# Sheet3.net
KiCad netlist of a schematic drawn in Altium Designer
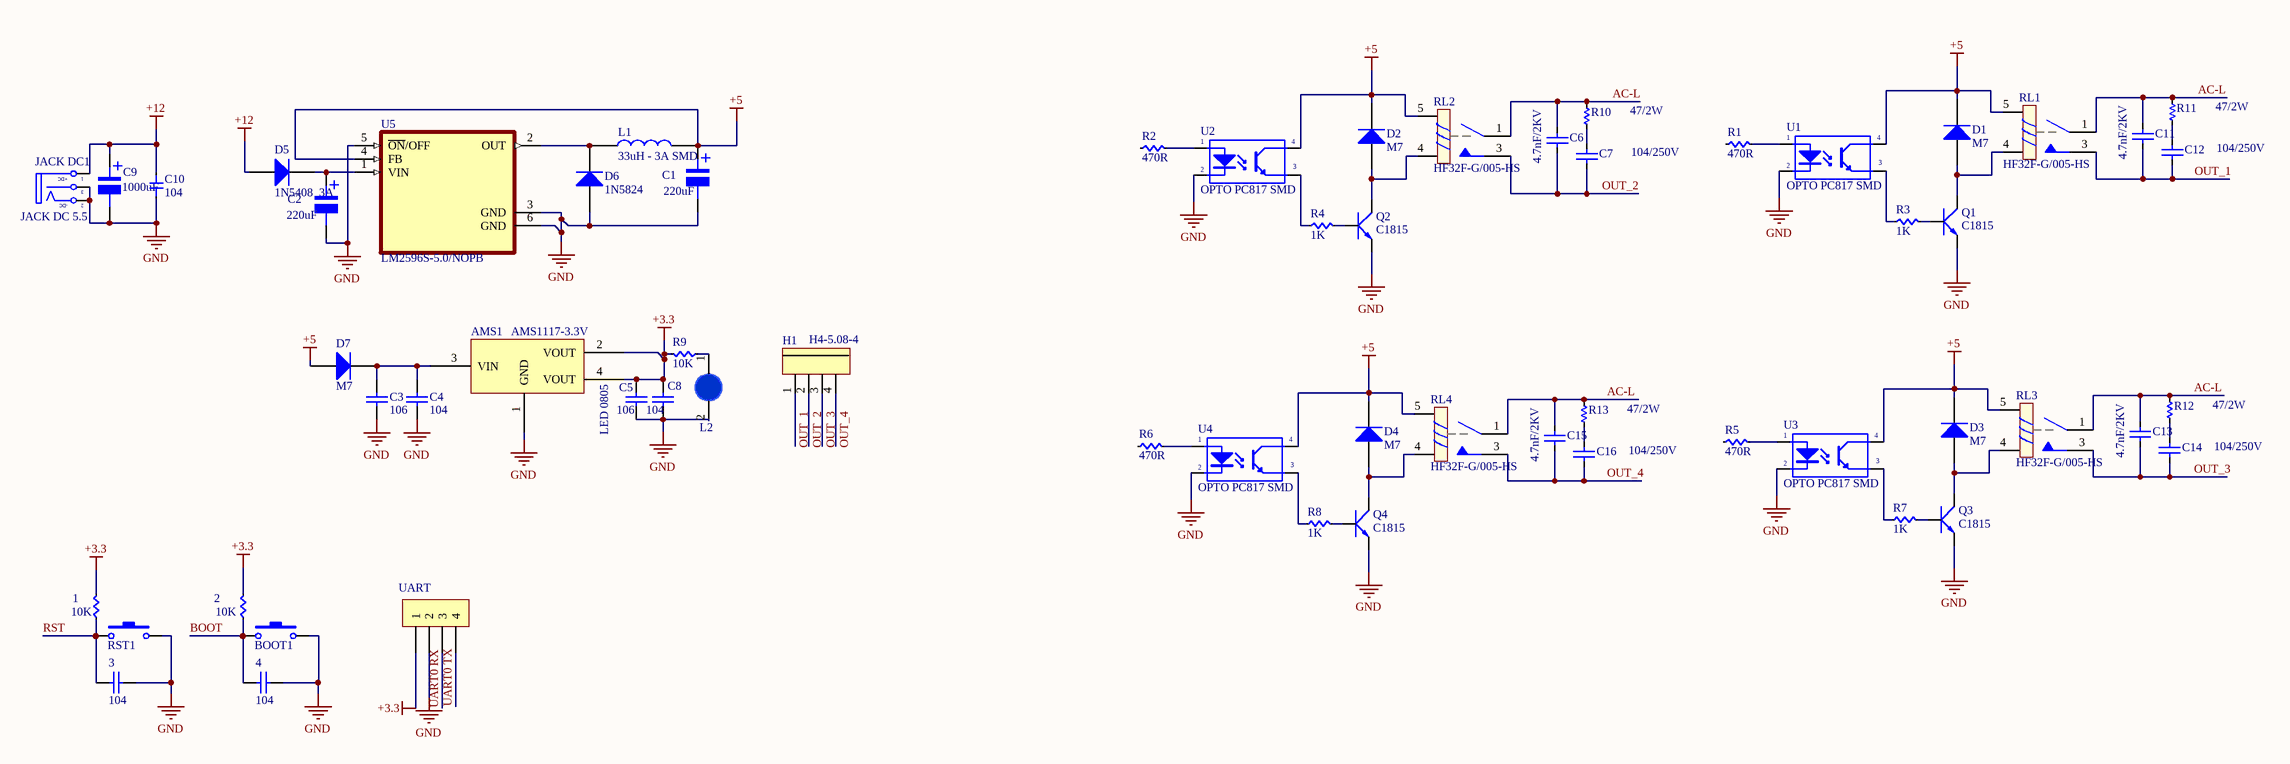
[diagram p0: Sheet3.SchDoc]

(export (version "E")
  (design (tool "Eeschema 10.0.6"))
  (components
    (comp (ref "1")
      (value "10K")
      (footprint "RES 0805")
      (description "RES SMD 0805")
      (fields
        (field (name "MANUFACTURER") "Vishay Dale")
        (field (name "MANUFACTURER PART NUMBER") "CRCW040210K0FKED")
      )
      (libsource (lib "Altium_Lib_by_KhueNguyenCreator") (part "RES 0805"))
    )
    (comp (ref "2")
      (value "10K")
      (footprint "RES 0805")
      (description "RES SMD 0805")
      (fields
        (field (name "MANUFACTURER") "Vishay Dale")
        (field (name "MANUFACTURER PART NUMBER") "CRCW040210K0FKED")
      )
      (libsource (lib "Altium_Lib_by_KhueNguyenCreator") (part "RES 0805"))
    )
    (comp (ref "3")
      (value "104")
      (footprint "tu 0805")
      (description "Dán")
      (libsource (lib "Altium_Lib_by_KhueNguyenCreator") (part "Tu 0805 104 50V 10%"))
    )
    (comp (ref "4")
      (value "104")
      (footprint "tu 0805")
      (description "Dán")
      (libsource (lib "Altium_Lib_by_KhueNguyenCreator") (part "Tu 0805 104 50V 10%"))
    )
    (comp (ref "AMS1")
      (value "AMS1117-3.3V")
      (footprint "SOT223")
      (description "Dán")
      (libsource (lib "Altium_Lib_by_KhueNguyenCreator") (part "AMS1117 SMD"))
    )
    (comp (ref "BOOT1")
      (value "Nut Nhan 2 Chan SMD 3x6x2.5")
      (footprint "Nut Nhan 2 Chan SMD 3x6x2.5")
      (libsource (lib "Altium_Lib_by_KhueNguyenCreator") (part "Nut Nhan 2 Chan SMD 3x6x2.5"))
    )
    (comp (ref "C1")
      (value "220uF")
      (footprint "tu nhom 10 (G)")
      (description "Dán")
      (libsource (lib "Altium_Lib_by_KhueNguyenCreator") (part "Tu Nhom 470uF 35V"))
    )
    (comp (ref "C2")
      (value "220uF")
      (footprint "tu nhom 10 (G)")
      (description "Dán")
      (libsource (lib "Altium_Lib_by_KhueNguyenCreator") (part "Tu Nhom 470uF 35V"))
    )
    (comp (ref "C3")
      (value "106")
      (footprint "tu 0805")
      (description "Dán")
      (libsource (lib "Altium_Lib_by_KhueNguyenCreator") (part "Tu 0805 106 16V 10%"))
    )
    (comp (ref "C4")
      (value "104")
      (footprint "tu 0805")
      (description "Dán")
      (libsource (lib "Altium_Lib_by_KhueNguyenCreator") (part "Tu 0805 104 50V 10%"))
    )
    (comp (ref "C5")
      (value "106")
      (footprint "tu 0805")
      (description "Dán")
      (libsource (lib "Altium_Lib_by_KhueNguyenCreator") (part "Tu 0805 106 16V 10%"))
    )
    (comp (ref "C6")
      (value "4.7nF/2KV")
      (footprint "Cap 6.35mm")
      (description "Capacitor")
      (libsource (lib "iuh-thuc-hanh") (part "CN"))
    )
    (comp (ref "C7")
      (value "104/250V")
      (footprint "Cap 10mm")
      (description "Capacitor")
      (libsource (lib "iuh-thuc-hanh") (part "CN"))
    )
    (comp (ref "C8")
      (value "104")
      (footprint "tu 0805")
      (description "Dán")
      (libsource (lib "Altium_Lib_by_KhueNguyenCreator") (part "Tu 0805 106 16V 10%"))
    )
    (comp (ref "C9")
      (value "1000uF")
      (footprint "tu nhom 10 (G)")
      (description "Dán")
      (libsource (lib "Altium_Lib_by_KhueNguyenCreator") (part "Tu Nhom 1000uF 10V"))
    )
    (comp (ref "C10")
      (value "104")
      (footprint "Cap 0603")
      (description "Capacitor SMD 0603")
      (libsource (lib "Altium_Lib_by_KhueNguyenCreator") (part "Cap 0603"))
    )
    (comp (ref "C11")
      (value "4.7nF/2KV")
      (footprint "Cap 6.35mm")
      (description "Capacitor")
      (libsource (lib "iuh-thuc-hanh") (part "CN"))
    )
    (comp (ref "C12")
      (value "104/250V")
      (footprint "Cap 10mm")
      (description "Capacitor")
      (libsource (lib "iuh-thuc-hanh") (part "CN"))
    )
    (comp (ref "C13")
      (value "4.7nF/2KV")
      (footprint "Cap 6.35mm")
      (description "Capacitor")
      (libsource (lib "iuh-thuc-hanh") (part "CN"))
    )
    (comp (ref "C14")
      (value "104/250V")
      (footprint "Cap 10mm")
      (description "Capacitor")
      (libsource (lib "iuh-thuc-hanh") (part "CN"))
    )
    (comp (ref "C15")
      (value "4.7nF/2KV")
      (footprint "Cap 6.35mm")
      (description "Capacitor")
      (libsource (lib "iuh-thuc-hanh") (part "CN"))
    )
    (comp (ref "C16")
      (value "104/250V")
      (footprint "Cap 10mm")
      (description "Capacitor")
      (libsource (lib "iuh-thuc-hanh") (part "CN"))
    )
    (comp (ref "D1")
      (value "M7")
      (footprint "DIODE SMA")
      (description "Dán")
      (libsource (lib "Altium_Lib_by_KhueNguyenCreator") (part "Diode M7 ( 4007 )"))
    )
    (comp (ref "D2")
      (value "M7")
      (footprint "DIODE SMA")
      (description "Dán")
      (libsource (lib "Altium_Lib_by_KhueNguyenCreator") (part "Diode M7 ( 4007 )"))
    )
    (comp (ref "D3")
      (value "M7")
      (footprint "DIODE SMA")
      (description "Dán")
      (libsource (lib "Altium_Lib_by_KhueNguyenCreator") (part "Diode M7 ( 4007 )"))
    )
    (comp (ref "D4")
      (value "M7")
      (footprint "DIODE SMA")
      (description "Dán")
      (libsource (lib "Altium_Lib_by_KhueNguyenCreator") (part "Diode M7 ( 4007 )"))
    )
    (comp (ref "D5")
      (value "1N5408  3A")
      (footprint "DIODE SMA")
      (description "Dán")
      (libsource (lib "Altium_Lib_by_KhueNguyenCreator") (part "Diode M7 ( 4007 )"))
    )
    (comp (ref "D6")
      (value "1N5824")
      (footprint "DIODE SMA")
      (description "Dán")
      (libsource (lib "Altium_Lib_by_KhueNguyenCreator") (part "Diode SS34 ( 1N5822 )"))
    )
    (comp (ref "D7")
      (value "M7")
      (footprint "DIODE SMA")
      (description "Dán")
      (libsource (lib "Altium_Lib_by_KhueNguyenCreator") (part "Diode M7 ( 4007 )"))
    )
    (comp (ref "H1")
      (value "H4-5.08-4")
      (footprint "KF-5.08-4")
      (libsource (lib "iuh-thuc-hanh") (part "KF-5.08-4-R Cong"))
    )
    (comp (ref "H2")
      (value "UART")
      (footprint "XH2.54M-4")
      (description "Cắm")
      (libsource (lib "Altium_Lib_by_KhueNguyenCreator") (part "Header 4P 2.54 Duc Thang"))
    )
    (comp (ref "JACK DC1")
      (value "JACK DC 5.5")
      (footprint "JACK DC 5.5")
      (libsource (lib "Altium_Lib_by_KhueNguyenCreator") (part "JACK DC 5.5"))
    )
    (comp (ref "L1")
      (value "33uH - 3A SMD")
      (footprint "Cuon Cam 12x12x10")
      (description "Dán")
      (libsource (lib "Altium_Lib_by_KhueNguyenCreator") (part "CUON CAM 100uH SMD"))
    )
    (comp (ref "L2")
      (value "LED 0805")
      (footprint "LED-0805-Blue")
      (description "Dán")
      (libsource (lib "Altium_Lib_by_KhueNguyenCreator") (part "LED 0805 Xanh Duong"))
    )
    (comp (ref "Q1")
      (value "C1815")
      (footprint "QTO-92")
      (description "NPN 600mW, ECB")
      (libsource (lib "syhaunguyen") (part "C1815"))
    )
    (comp (ref "Q2")
      (value "C1815")
      (footprint "QTO-92")
      (description "NPN 600mW, ECB")
      (libsource (lib "syhaunguyen") (part "C1815"))
    )
    (comp (ref "Q3")
      (value "C1815")
      (footprint "QTO-92")
      (description "NPN 600mW, ECB")
      (libsource (lib "syhaunguyen") (part "C1815"))
    )
    (comp (ref "Q4")
      (value "C1815")
      (footprint "QTO-92")
      (description "NPN 600mW, ECB")
      (libsource (lib "syhaunguyen") (part "C1815"))
    )
    (comp (ref "R1")
      (value "470R")
      (footprint "RES 0805")
      (description "RES SMD 0805")
      (fields
        (field (name "MANUFACTURER") "Vishay Dale")
        (field (name "MANUFACTURER PART NUMBER") "CRCW040210K0FKED")
      )
      (libsource (lib "Altium_Lib_by_KhueNguyenCreator") (part "RES 0805"))
    )
    (comp (ref "R2")
      (value "470R")
      (footprint "RES 0805")
      (description "RES SMD 0805")
      (fields
        (field (name "MANUFACTURER") "Vishay Dale")
        (field (name "MANUFACTURER PART NUMBER") "CRCW040210K0FKED")
      )
      (libsource (lib "Altium_Lib_by_KhueNguyenCreator") (part "RES 0805"))
    )
    (comp (ref "R3")
      (value "1K")
      (footprint "RES 0805")
      (description "RES SMD 0805")
      (fields
        (field (name "MANUFACTURER") "Vishay Dale")
        (field (name "MANUFACTURER PART NUMBER") "CRCW040210K0FKED")
      )
      (libsource (lib "Altium_Lib_by_KhueNguyenCreator") (part "RES 0805"))
    )
    (comp (ref "R4")
      (value "1K")
      (footprint "RES 0805")
      (description "RES SMD 0805")
      (fields
        (field (name "MANUFACTURER") "Vishay Dale")
        (field (name "MANUFACTURER PART NUMBER") "CRCW040210K0FKED")
      )
      (libsource (lib "Altium_Lib_by_KhueNguyenCreator") (part "RES 0805"))
    )
    (comp (ref "R5")
      (value "470R")
      (footprint "RES 0805")
      (description "RES SMD 0805")
      (fields
        (field (name "MANUFACTURER") "Vishay Dale")
        (field (name "MANUFACTURER PART NUMBER") "CRCW040210K0FKED")
      )
      (libsource (lib "Altium_Lib_by_KhueNguyenCreator") (part "RES 0805"))
    )
    (comp (ref "R6")
      (value "470R")
      (footprint "RES 0805")
      (description "RES SMD 0805")
      (fields
        (field (name "MANUFACTURER") "Vishay Dale")
        (field (name "MANUFACTURER PART NUMBER") "CRCW040210K0FKED")
      )
      (libsource (lib "Altium_Lib_by_KhueNguyenCreator") (part "RES 0805"))
    )
    (comp (ref "R7")
      (value "1K")
      (footprint "RES 0805")
      (description "RES SMD 0805")
      (fields
        (field (name "MANUFACTURER") "Vishay Dale")
        (field (name "MANUFACTURER PART NUMBER") "CRCW040210K0FKED")
      )
      (libsource (lib "Altium_Lib_by_KhueNguyenCreator") (part "RES 0805"))
    )
    (comp (ref "R8")
      (value "1K")
      (footprint "RES 0805")
      (description "RES SMD 0805")
      (fields
        (field (name "MANUFACTURER") "Vishay Dale")
        (field (name "MANUFACTURER PART NUMBER") "CRCW040210K0FKED")
      )
      (libsource (lib "Altium_Lib_by_KhueNguyenCreator") (part "RES 0805"))
    )
    (comp (ref "R9")
      (value "10K")
      (footprint "RES 0805")
      (description "RES SMD 0805")
      (fields
        (field (name "MANUFACTURER") "Vishay Dale")
        (field (name "MANUFACTURER PART NUMBER") "CRCW040210K0FKED")
      )
      (libsource (lib "Altium_Lib_by_KhueNguyenCreator") (part "RES 0805"))
    )
    (comp (ref "R10") (value "47/2W") (footprint "RES-1W") (libsource (lib "iuh-thuc-hanh") (part "Res")))
    (comp (ref "R11") (value "47/2W") (footprint "RES-1W") (libsource (lib "iuh-thuc-hanh") (part "Res")))
    (comp (ref "R12") (value "47/2W") (footprint "RES-1W") (libsource (lib "iuh-thuc-hanh") (part "Res")))
    (comp (ref "R13") (value "47/2W") (footprint "RES-1W") (libsource (lib "iuh-thuc-hanh") (part "Res")))
    (comp (ref "RL1")
      (value "HF32F-G/005-HS")
      (footprint "HF32F-G")
      (description "Relay hongfa 10A 4P HF32F-G/005-HS")
      (libsource (lib "iuh-thuc-hanh") (part "Relay HF 10A"))
    )
    (comp (ref "RL2")
      (value "HF32F-G/005-HS")
      (footprint "HF32F-G")
      (description "Relay hongfa 10A 4P HF32F-G/005-HS")
      (libsource (lib "iuh-thuc-hanh") (part "Relay HF 10A"))
    )
    (comp (ref "RL3")
      (value "HF32F-G/005-HS")
      (footprint "HF32F-G")
      (description "Relay hongfa 10A 4P HF32F-G/005-HS")
      (libsource (lib "iuh-thuc-hanh") (part "Relay HF 10A"))
    )
    (comp (ref "RL4")
      (value "HF32F-G/005-HS")
      (footprint "HF32F-G")
      (description "Relay hongfa 10A 4P HF32F-G/005-HS")
      (libsource (lib "iuh-thuc-hanh") (part "Relay HF 10A"))
    )
    (comp (ref "RST1")
      (value "Nut Nhan 2 Chan SMD 3x6x2.5")
      (footprint "Nut Nhan 2 Chan SMD 3x6x2.5")
      (libsource (lib "Altium_Lib_by_KhueNguyenCreator") (part "Nut Nhan 2 Chan SMD 3x6x2.5"))
    )
    (comp (ref "U1")
      (value "OPTO PC817 SMD")
      (footprint "SOP4")
      (description "Single Opto")
      (libsource (lib "Altium_Lib_by_KhueNguyenCreator") (part "OPTO PC817 SMD"))
    )
    (comp (ref "U2")
      (value "OPTO PC817 SMD")
      (footprint "SOP4")
      (description "Single Opto")
      (libsource (lib "Altium_Lib_by_KhueNguyenCreator") (part "OPTO PC817 SMD"))
    )
    (comp (ref "U3")
      (value "OPTO PC817 SMD")
      (footprint "SOP4")
      (description "Single Opto")
      (libsource (lib "Altium_Lib_by_KhueNguyenCreator") (part "OPTO PC817 SMD"))
    )
    (comp (ref "U4")
      (value "OPTO PC817 SMD")
      (footprint "SOP4")
      (description "Single Opto")
      (libsource (lib "Altium_Lib_by_KhueNguyenCreator") (part "OPTO PC817 SMD"))
    )
    (comp (ref "U5")
      (value "LM2596S-5.0/NOPB")
      (footprint "VREG_LM2596S-12/NOPB")
      (description "SIMPLE SWITCHERÂ® 4.5V to 40V, 3A Low Component Count Step-Down Regulator")
      (fields (field (name "MF") "Texas Instruments") (field (name "MP") "LM2596S-12/NOPB"))
      (libsource (lib "TuHap") (part "LM2596S-12/NOPB"))
    )
  )
  (nets
    (net (code "1") (name "+3.3") (class "Default")
      (node (ref "1") (pin "2") (pinfunction "2_2") (pintype "passive"))
      (node (ref "2") (pin "2") (pinfunction "2_2") (pintype "passive"))
      (node (ref "AMS1") (pin "2") (pinfunction "VOUT_2") (pintype "passive"))
      (node (ref "AMS1") (pin "4") (pinfunction "VOUT_4") (pintype "passive"))
      (node (ref "C5") (pin "1") (pinfunction "1_1") (pintype "passive"))
      (node (ref "C8") (pin "1") (pinfunction "1_1") (pintype "passive"))
      (node (ref "H2") (pin "1") (pinfunction "1_1") (pintype "passive"))
      (node (ref "R9") (pin "2") (pinfunction "2_2") (pintype "passive"))
    )
    (net (code "2") (name "+5") (class "Default")
      (node (ref "C1") (pin "1") (pinfunction "1_1") (pintype "passive"))
      (node (ref "D1") (pin "2") (pinfunction "K_2") (pintype "passive"))
      (node (ref "D2") (pin "2") (pinfunction "K_2") (pintype "passive"))
      (node (ref "D3") (pin "2") (pinfunction "K_2") (pintype "passive"))
      (node (ref "D4") (pin "2") (pinfunction "K_2") (pintype "passive"))
      (node (ref "D7") (pin "1") (pinfunction "A_1") (pintype "passive"))
      (node (ref "L1") (pin "2") (pinfunction "2_2") (pintype "passive"))
      (node (ref "RL1") (pin "5") (pinfunction "5_5") (pintype "passive"))
      (node (ref "RL2") (pin "5") (pinfunction "5_5") (pintype "passive"))
      (node (ref "RL3") (pin "5") (pinfunction "5_5") (pintype "passive"))
      (node (ref "RL4") (pin "5") (pinfunction "5_5") (pintype "passive"))
      (node (ref "U1") (pin "4") (pinfunction "C_4") (pintype "passive"))
      (node (ref "U2") (pin "4") (pinfunction "C_4") (pintype "passive"))
      (node (ref "U3") (pin "4") (pinfunction "C_4") (pintype "passive"))
      (node (ref "U4") (pin "4") (pinfunction "C_4") (pintype "passive"))
      (node (ref "U5") (pin "4") (pinfunction "FB_4") (pintype "input"))
    )
    (net (code "3") (name "+12") (class "Default")
      (node (ref "C10") (pin "1") (pinfunction "1_1") (pintype "passive"))
      (node (ref "C9") (pin "1") (pinfunction "1_1") (pintype "passive"))
      (node (ref "D5") (pin "1") (pinfunction "A_1") (pintype "passive"))
      (node (ref "JACK DC1") (pin "1") (pinfunction "T_1") (pintype "passive"))
    )
    (net (code "4") (name "/AC-L") (class "Default")
      (node (ref "C11") (pin "1") (pinfunction "1_1") (pintype "passive"))
      (node (ref "C13") (pin "1") (pinfunction "1_1") (pintype "passive"))
      (node (ref "C15") (pin "1") (pinfunction "1_1") (pintype "passive"))
      (node (ref "C6") (pin "1") (pinfunction "1_1") (pintype "passive"))
      (node (ref "R10") (pin "1") (pinfunction "1_1") (pintype "passive"))
      (node (ref "R11") (pin "1") (pinfunction "1_1") (pintype "passive"))
      (node (ref "R12") (pin "1") (pinfunction "1_1") (pintype "passive"))
      (node (ref "R13") (pin "1") (pinfunction "1_1") (pintype "passive"))
      (node (ref "RL1") (pin "1") (pinfunction "1_1") (pintype "passive"))
      (node (ref "RL2") (pin "1") (pinfunction "1_1") (pintype "passive"))
      (node (ref "RL3") (pin "1") (pinfunction "1_1") (pintype "passive"))
      (node (ref "RL4") (pin "1") (pinfunction "1_1") (pintype "passive"))
    )
    (net (code "5") (name "/BOOT") (class "Default")
      (node (ref "2") (pin "1") (pinfunction "1_1") (pintype "passive"))
      (node (ref "4") (pin "1") (pinfunction "1_1") (pintype "passive"))
      (node (ref "BOOT1") (pin "1") (pinfunction "1_1") (pintype "passive"))
    )
    (net (code "6") (name "/OUT_1") (class "Default")
      (node (ref "C11") (pin "2") (pinfunction "2_2") (pintype "passive"))
      (node (ref "C12") (pin "1") (pinfunction "1_1") (pintype "passive"))
      (node (ref "H1") (pin "1") (pinfunction "1_1") (pintype "passive"))
      (node (ref "RL1") (pin "3") (pinfunction "3_3") (pintype "passive"))
    )
    (net (code "7") (name "/OUT_2") (class "Default")
      (node (ref "C6") (pin "2") (pinfunction "2_2") (pintype "passive"))
      (node (ref "C7") (pin "1") (pinfunction "1_1") (pintype "passive"))
      (node (ref "H1") (pin "2") (pinfunction "2_2") (pintype "passive"))
      (node (ref "RL2") (pin "3") (pinfunction "3_3") (pintype "passive"))
    )
    (net (code "8") (name "/OUT_3") (class "Default")
      (node (ref "C13") (pin "2") (pinfunction "2_2") (pintype "passive"))
      (node (ref "C14") (pin "1") (pinfunction "1_1") (pintype "passive"))
      (node (ref "H1") (pin "3") (pinfunction "3_3") (pintype "passive"))
      (node (ref "RL3") (pin "3") (pinfunction "3_3") (pintype "passive"))
    )
    (net (code "9") (name "/OUT_4") (class "Default")
      (node (ref "C15") (pin "2") (pinfunction "2_2") (pintype "passive"))
      (node (ref "C16") (pin "1") (pinfunction "1_1") (pintype "passive"))
      (node (ref "H1") (pin "4") (pinfunction "4_4") (pintype "passive"))
      (node (ref "RL4") (pin "3") (pinfunction "3_3") (pintype "passive"))
    )
    (net (code "10") (name "/RST") (class "Default")
      (node (ref "1") (pin "1") (pinfunction "1_1") (pintype "passive"))
      (node (ref "3") (pin "1") (pinfunction "1_1") (pintype "passive"))
      (node (ref "RST1") (pin "1") (pinfunction "1_1") (pintype "passive"))
    )
    (net (code "11") (name "/UART0 RX") (class "Default")
      (node (ref "H2") (pin "3") (pinfunction "3_3") (pintype "passive"))
    )
    (net (code "12") (name "/UART0 TX") (class "Default")
      (node (ref "H2") (pin "4") (pinfunction "4_4") (pintype "passive"))
    )
    (net (code "13") (name "GND") (class "Default")
      (node (ref "3") (pin "2") (pinfunction "2_2") (pintype "passive"))
      (node (ref "4") (pin "2") (pinfunction "2_2") (pintype "passive"))
      (node (ref "AMS1") (pin "1") (pinfunction "GND_1") (pintype "passive"))
      (node (ref "BOOT1") (pin "2") (pinfunction "2_2") (pintype "passive"))
      (node (ref "C1") (pin "2") (pinfunction "2_2") (pintype "passive"))
      (node (ref "C10") (pin "2") (pinfunction "2_2") (pintype "passive"))
      (node (ref "C2") (pin "2") (pinfunction "2_2") (pintype "passive"))
      (node (ref "C3") (pin "2") (pinfunction "2_2") (pintype "passive"))
      (node (ref "C4") (pin "2") (pinfunction "2_2") (pintype "passive"))
      (node (ref "C5") (pin "2") (pinfunction "2_2") (pintype "passive"))
      (node (ref "C8") (pin "2") (pinfunction "2_2") (pintype "passive"))
      (node (ref "C9") (pin "2") (pinfunction "2_2") (pintype "passive"))
      (node (ref "D6") (pin "1") (pinfunction "A_1") (pintype "passive"))
      (node (ref "H2") (pin "2") (pinfunction "2_2") (pintype "passive"))
      (node (ref "JACK DC1") (pin "2") (pinfunction "TN_2") (pintype "passive"))
      (node (ref "JACK DC1") (pin "3") (pinfunction "S_3") (pintype "power_in"))
      (node (ref "L2") (pin "2") (pinfunction "K_2") (pintype "passive"))
      (node (ref "Q1") (pin "1") (pinfunction "E_1") (pintype "passive"))
      (node (ref "Q2") (pin "1") (pinfunction "E_1") (pintype "passive"))
      (node (ref "Q3") (pin "1") (pinfunction "E_1") (pintype "passive"))
      (node (ref "Q4") (pin "1") (pinfunction "E_1") (pintype "passive"))
      (node (ref "RST1") (pin "2") (pinfunction "2_2") (pintype "passive"))
      (node (ref "U1") (pin "2") (pinfunction "K_2") (pintype "passive"))
      (node (ref "U2") (pin "2") (pinfunction "K_2") (pintype "passive"))
      (node (ref "U3") (pin "2") (pinfunction "K_2") (pintype "passive"))
      (node (ref "U4") (pin "2") (pinfunction "K_2") (pintype "passive"))
      (node (ref "U5") (pin "3") (pinfunction "GND_3") (pintype "power_in"))
      (node (ref "U5") (pin "5") (pinfunction "~{ON}/OFF_5") (pintype "input"))
      (node (ref "U5") (pin "6") (pinfunction "GND_6") (pintype "power_in"))
    )
    (net (code "14") (name "Net-(AMS1-VIN)") (class "Default")
      (node (ref "AMS1") (pin "3") (pinfunction "VIN_3") (pintype "passive"))
      (node (ref "C3") (pin "1") (pinfunction "1_1") (pintype "passive"))
      (node (ref "C4") (pin "1") (pinfunction "1_1") (pintype "passive"))
      (node (ref "D7") (pin "2") (pinfunction "K_2") (pintype "passive"))
    )
    (net (code "15") (name "Net-(C7-Pad2)") (class "Default")
      (node (ref "C7") (pin "2") (pinfunction "2_2") (pintype "passive"))
      (node (ref "R10") (pin "2") (pinfunction "2_2") (pintype "passive"))
    )
    (net (code "16") (name "Net-(C12-Pad2)") (class "Default")
      (node (ref "C12") (pin "2") (pinfunction "2_2") (pintype "passive"))
      (node (ref "R11") (pin "2") (pinfunction "2_2") (pintype "passive"))
    )
    (net (code "17") (name "Net-(C14-Pad2)") (class "Default")
      (node (ref "C14") (pin "2") (pinfunction "2_2") (pintype "passive"))
      (node (ref "R12") (pin "2") (pinfunction "2_2") (pintype "passive"))
    )
    (net (code "18") (name "Net-(C16-Pad2)") (class "Default")
      (node (ref "C16") (pin "2") (pinfunction "2_2") (pintype "passive"))
      (node (ref "R13") (pin "2") (pinfunction "2_2") (pintype "passive"))
    )
    (net (code "19") (name "Net-(D1-A)") (class "Default")
      (node (ref "D1") (pin "1") (pinfunction "A_1") (pintype "passive"))
      (node (ref "Q1") (pin "2") (pinfunction "C_2") (pintype "passive"))
      (node (ref "RL1") (pin "4") (pinfunction "4_4") (pintype "passive"))
    )
    (net (code "20") (name "Net-(D2-A)") (class "Default")
      (node (ref "D2") (pin "1") (pinfunction "A_1") (pintype "passive"))
      (node (ref "Q2") (pin "2") (pinfunction "C_2") (pintype "passive"))
      (node (ref "RL2") (pin "4") (pinfunction "4_4") (pintype "passive"))
    )
    (net (code "21") (name "Net-(D3-A)") (class "Default")
      (node (ref "D3") (pin "1") (pinfunction "A_1") (pintype "passive"))
      (node (ref "Q3") (pin "2") (pinfunction "C_2") (pintype "passive"))
      (node (ref "RL3") (pin "4") (pinfunction "4_4") (pintype "passive"))
    )
    (net (code "22") (name "Net-(D4-A)") (class "Default")
      (node (ref "D4") (pin "1") (pinfunction "A_1") (pintype "passive"))
      (node (ref "Q4") (pin "2") (pinfunction "C_2") (pintype "passive"))
      (node (ref "RL4") (pin "4") (pinfunction "4_4") (pintype "passive"))
    )
    (net (code "23") (name "Net-(D5-K)") (class "Default")
      (node (ref "C2") (pin "1") (pinfunction "1_1") (pintype "passive"))
      (node (ref "D5") (pin "2") (pinfunction "K_2") (pintype "passive"))
      (node (ref "U5") (pin "1") (pinfunction "VIN_1") (pintype "input"))
    )
    (net (code "24") (name "Net-(D6-K)") (class "Default")
      (node (ref "D6") (pin "2") (pinfunction "K_2") (pintype "passive"))
      (node (ref "L1") (pin "1") (pinfunction "1_1") (pintype "passive"))
      (node (ref "U5") (pin "2") (pinfunction "OUT_2") (pintype "output"))
    )
    (net (code "25") (name "Net-(L2-A)") (class "Default")
      (node (ref "L2") (pin "1") (pinfunction "A_1") (pintype "passive"))
      (node (ref "R9") (pin "1") (pinfunction "1_1") (pintype "passive"))
    )
    (net (code "26") (name "Net-(Q1-B)") (class "Default")
      (node (ref "Q1") (pin "3") (pinfunction "B_3") (pintype "passive"))
      (node (ref "R3") (pin "2") (pinfunction "2_2") (pintype "passive"))
    )
    (net (code "27") (name "Net-(Q2-B)") (class "Default")
      (node (ref "Q2") (pin "3") (pinfunction "B_3") (pintype "passive"))
      (node (ref "R4") (pin "2") (pinfunction "2_2") (pintype "passive"))
    )
    (net (code "28") (name "Net-(Q3-B)") (class "Default")
      (node (ref "Q3") (pin "3") (pinfunction "B_3") (pintype "passive"))
      (node (ref "R7") (pin "2") (pinfunction "2_2") (pintype "passive"))
    )
    (net (code "29") (name "Net-(Q4-B)") (class "Default")
      (node (ref "Q4") (pin "3") (pinfunction "B_3") (pintype "passive"))
      (node (ref "R8") (pin "2") (pinfunction "2_2") (pintype "passive"))
    )
    (net (code "30") (name "Net-(U1-A)") (class "Default")
      (node (ref "R1") (pin "2") (pinfunction "2_2") (pintype "passive"))
      (node (ref "U1") (pin "1") (pinfunction "A_1") (pintype "passive"))
    )
    (net (code "31") (name "Net-(U1-E)") (class "Default")
      (node (ref "R3") (pin "1") (pinfunction "1_1") (pintype "passive"))
      (node (ref "U1") (pin "3") (pinfunction "E_3") (pintype "passive"))
    )
    (net (code "32") (name "Net-(U2-A)") (class "Default")
      (node (ref "R2") (pin "2") (pinfunction "2_2") (pintype "passive"))
      (node (ref "U2") (pin "1") (pinfunction "A_1") (pintype "passive"))
    )
    (net (code "33") (name "Net-(U2-E)") (class "Default")
      (node (ref "R4") (pin "1") (pinfunction "1_1") (pintype "passive"))
      (node (ref "U2") (pin "3") (pinfunction "E_3") (pintype "passive"))
    )
    (net (code "34") (name "Net-(U3-A)") (class "Default")
      (node (ref "R5") (pin "2") (pinfunction "2_2") (pintype "passive"))
      (node (ref "U3") (pin "1") (pinfunction "A_1") (pintype "passive"))
    )
    (net (code "35") (name "Net-(U3-E)") (class "Default")
      (node (ref "R7") (pin "1") (pinfunction "1_1") (pintype "passive"))
      (node (ref "U3") (pin "3") (pinfunction "E_3") (pintype "passive"))
    )
    (net (code "36") (name "Net-(U4-A)") (class "Default")
      (node (ref "R6") (pin "2") (pinfunction "2_2") (pintype "passive"))
      (node (ref "U4") (pin "1") (pinfunction "A_1") (pintype "passive"))
    )
    (net (code "37") (name "Net-(U4-E)") (class "Default")
      (node (ref "R8") (pin "1") (pinfunction "1_1") (pintype "passive"))
      (node (ref "U4") (pin "3") (pinfunction "E_3") (pintype "passive"))
    )
    (net (code "38") (name "unconnected-(R1-Pad1)") (class "Default")
      (node (ref "R1") (pin "1") (pinfunction "1_1") (pintype "passive"))
    )
    (net (code "39") (name "unconnected-(R2-Pad1)") (class "Default")
      (node (ref "R2") (pin "1") (pinfunction "1_1") (pintype "passive"))
    )
    (net (code "40") (name "unconnected-(R5-Pad1)") (class "Default")
      (node (ref "R5") (pin "1") (pinfunction "1_1") (pintype "passive"))
    )
    (net (code "41") (name "unconnected-(R6-Pad1)") (class "Default")
      (node (ref "R6") (pin "1") (pinfunction "1_1") (pintype "passive"))
    )
  )
)
